# InterfaceConfiguracao.net
KiCad netlist of a schematic drawn in Altium Designer
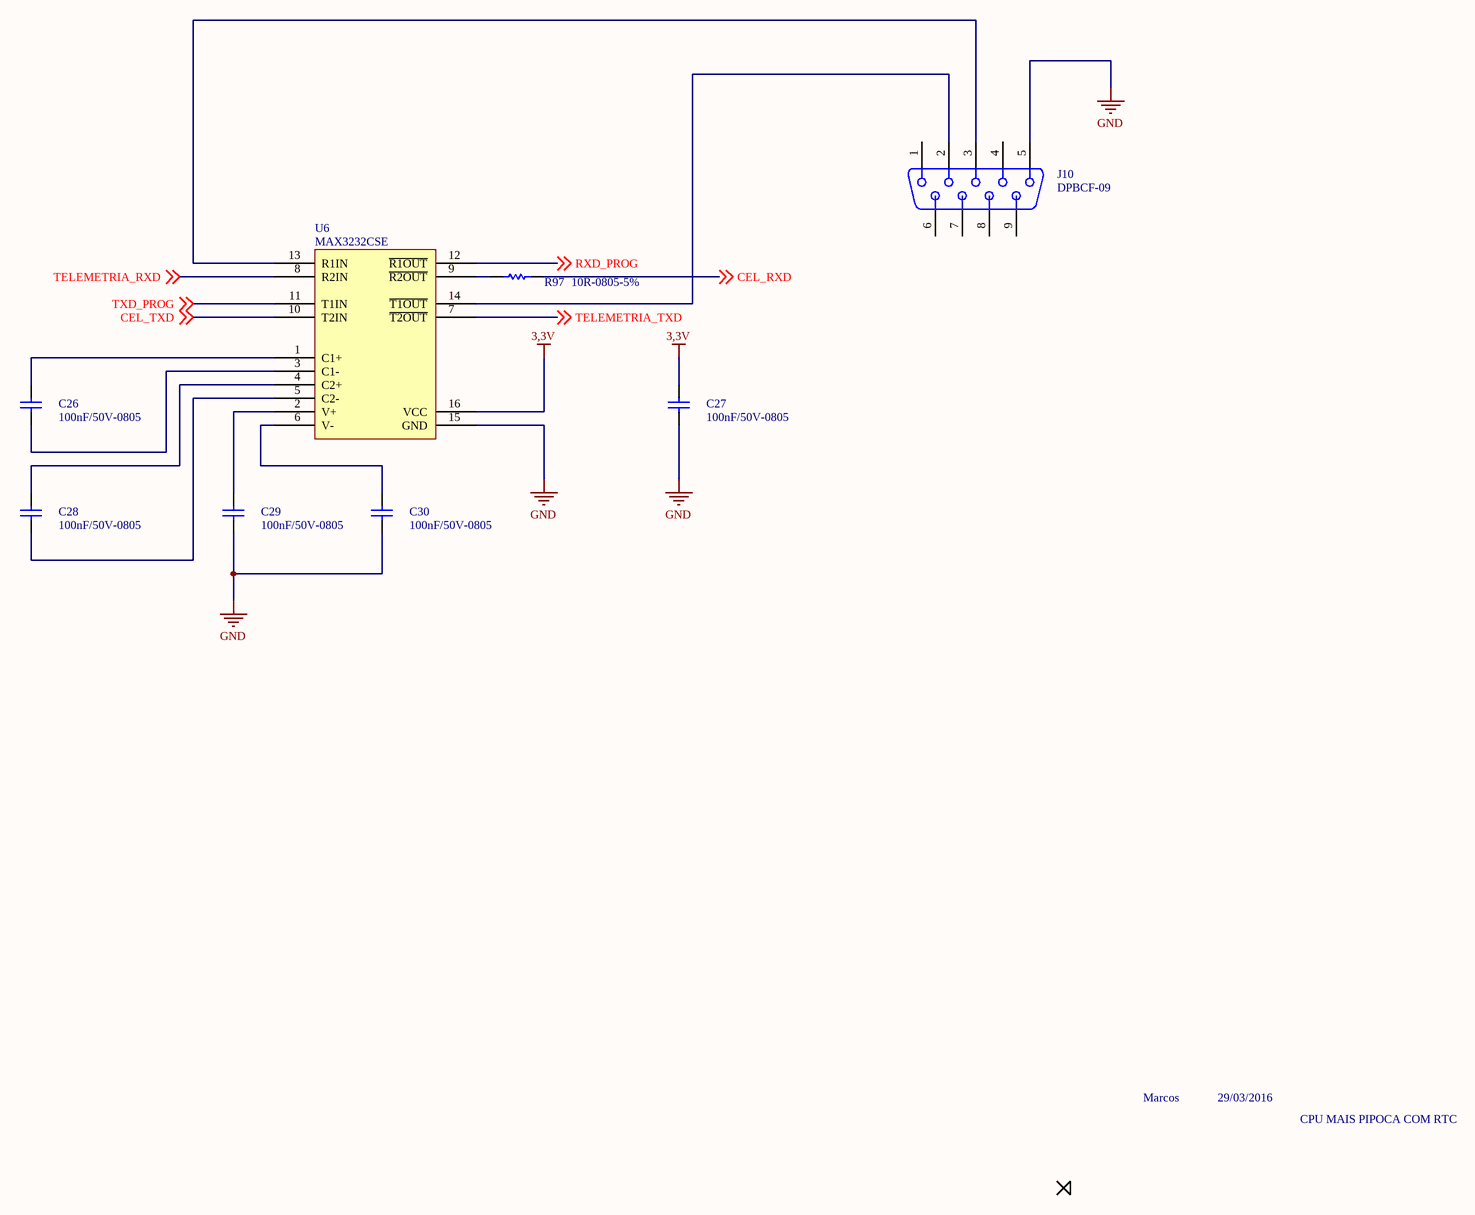
[diagram p0: InterfaceConfiguracao.SchDoc]

(export (version "E")
  (design (tool "Eeschema 10.0.6"))
  (components
    (comp (ref "C26")
      (value "100nF/50V-0805")
      (footprint "0805-REVISADO O")
      (description "100nF/50-0805-NPO")
      (libsource (lib "AquinoLib") (part "100nF/50-0805-NPO"))
    )
    (comp (ref "C27")
      (value "100nF/50V-0805")
      (footprint "0805-REVISADO O")
      (description "100nF/50-0805-NPO")
      (libsource (lib "AquinoLib") (part "100nF/50-0805-NPO"))
    )
    (comp (ref "C28")
      (value "100nF/50V-0805")
      (footprint "0805-REVISADO O")
      (description "100nF/50-0805-NPO")
      (libsource (lib "AquinoLib") (part "100nF/50-0805-NPO"))
    )
    (comp (ref "C29")
      (value "100nF/50V-0805")
      (footprint "0805-REVISADO O")
      (description "100nF/50-0805-NPO")
      (libsource (lib "AquinoLib") (part "100nF/50-0805-NPO"))
    )
    (comp (ref "C30")
      (value "100nF/50V-0805")
      (footprint "0805-REVISADO O")
      (description "100nF/50-0805-NPO")
      (libsource (lib "AquinoLib") (part "100nF/50-0805-NPO"))
    )
    (comp (ref "J10")
      (value "DPBCF-09")
      (footprint "DB9-FÊMEA MONTA_DB9-FÊMEA_MONTAGEM_EM_PCI_180(Primary)")
      (description "DBPCF-09")
      (libsource (lib "ChaveDigital3") (part "DB-9 - FÊMEA 180º MONTAGEM EM PCI"))
    )
    (comp (ref "R97")
      (value "10R-0805-5%")
      (footprint "0805-REVISADO O")
      (libsource (lib "AquinoLib") (part "10R-0805-5%"))
    )
    (comp (ref "U6")
      (value "MAX3232CSE")
      (footprint "SOIC 16 PINOS")
      (libsource (lib "ChaveDigital3") (part "MAX3232CSE"))
    )
  )
  (nets
    (net (code "1") (name "3,3V") (class "Default")
      (node (ref "C27") (pin "2") (pinfunction "2_2") (pintype "passive"))
      (node (ref "U6") (pin "16") (pinfunction "VCC_16") (pintype "passive"))
    )
    (net (code "2") (name "CEL_RXD") (class "Default")
      (node (ref "R97") (pin "2") (pinfunction "2_2") (pintype "passive"))
    )
    (net (code "3") (name "CEL_TXD") (class "Default")
      (node (ref "U6") (pin "10") (pinfunction "T2IN_10") (pintype "passive"))
    )
    (net (code "4") (name "GND") (class "Default")
      (node (ref "C27") (pin "1") (pinfunction "1_1") (pintype "passive"))
      (node (ref "C29") (pin "1") (pinfunction "1_1") (pintype "passive"))
      (node (ref "C30") (pin "1") (pinfunction "1_1") (pintype "passive"))
      (node (ref "J10") (pin "5") (pinfunction "5_5") (pintype "passive"))
      (node (ref "U6") (pin "15") (pinfunction "GND_15") (pintype "passive"))
    )
    (net (code "5") (name "Net-(U6-C1+)") (class "Default")
      (node (ref "C26") (pin "2") (pinfunction "2_2") (pintype "passive"))
      (node (ref "U6") (pin "1") (pinfunction "C1+_1") (pintype "passive"))
    )
    (net (code "6") (name "Net-(U6-C1-)") (class "Default")
      (node (ref "C26") (pin "1") (pinfunction "1_1") (pintype "passive"))
      (node (ref "U6") (pin "3") (pinfunction "C1-_3") (pintype "passive"))
    )
    (net (code "7") (name "Net-(U6-C2+)") (class "Default")
      (node (ref "C28") (pin "2") (pinfunction "2_2") (pintype "passive"))
      (node (ref "U6") (pin "4") (pinfunction "C2+_4") (pintype "passive"))
    )
    (net (code "8") (name "Net-(U6-C2-)") (class "Default")
      (node (ref "C28") (pin "1") (pinfunction "1_1") (pintype "passive"))
      (node (ref "U6") (pin "5") (pinfunction "C2-_5") (pintype "passive"))
    )
    (net (code "9") (name "Net-(U6-R1IN)") (class "Default")
      (node (ref "J10") (pin "3") (pinfunction "3_3") (pintype "passive"))
      (node (ref "U6") (pin "13") (pinfunction "R1IN_13") (pintype "passive"))
    )
    (net (code "10") (name "Net-(U6-V+)") (class "Default")
      (node (ref "C29") (pin "2") (pinfunction "2_2") (pintype "passive"))
      (node (ref "U6") (pin "2") (pinfunction "V+_2") (pintype "passive"))
    )
    (net (code "11") (name "Net-(U6-V-)") (class "Default")
      (node (ref "C30") (pin "2") (pinfunction "2_2") (pintype "passive"))
      (node (ref "U6") (pin "6") (pinfunction "V-_6") (pintype "passive"))
    )
    (net (code "12") (name "Net-(U6-~{R2OUT})") (class "Default")
      (node (ref "R97") (pin "1") (pinfunction "1_1") (pintype "passive"))
      (node (ref "U6") (pin "9") (pinfunction "~{R2OUT}_9") (pintype "passive"))
    )
    (net (code "13") (name "Net-(U6-~{T1OUT})") (class "Default")
      (node (ref "J10") (pin "2") (pinfunction "2_2") (pintype "passive"))
      (node (ref "U6") (pin "14") (pinfunction "~{T1OUT}_14") (pintype "passive"))
    )
    (net (code "14") (name "RXD_PROG") (class "Default")
      (node (ref "U6") (pin "12") (pinfunction "~{R1OUT}_12") (pintype "passive"))
    )
    (net (code "15") (name "TELEMETRIA_RXD") (class "Default")
      (node (ref "U6") (pin "8") (pinfunction "R2IN_8") (pintype "passive"))
    )
    (net (code "16") (name "TELEMETRIA_TXD") (class "Default")
      (node (ref "U6") (pin "7") (pinfunction "~{T2OUT}_7") (pintype "passive"))
    )
    (net (code "17") (name "TXD_PROG") (class "Default")
      (node (ref "U6") (pin "11") (pinfunction "T1IN_11") (pintype "passive"))
    )
    (net (code "18") (name "unconnected-(J10-Pad1)") (class "Default")
      (node (ref "J10") (pin "1") (pinfunction "1_1") (pintype "passive"))
    )
    (net (code "19") (name "unconnected-(J10-Pad4)") (class "Default")
      (node (ref "J10") (pin "4") (pinfunction "4_4") (pintype "passive"))
    )
    (net (code "20") (name "unconnected-(J10-Pad6)") (class "Default")
      (node (ref "J10") (pin "6") (pinfunction "6_6") (pintype "passive"))
    )
    (net (code "21") (name "unconnected-(J10-Pad7)") (class "Default")
      (node (ref "J10") (pin "7") (pinfunction "7_7") (pintype "passive"))
    )
    (net (code "22") (name "unconnected-(J10-Pad8)") (class "Default")
      (node (ref "J10") (pin "8") (pinfunction "8_8") (pintype "passive"))
    )
    (net (code "23") (name "unconnected-(J10-Pad9)") (class "Default")
      (node (ref "J10") (pin "9") (pinfunction "9_9") (pintype "passive"))
    )
  )
)
